# sch_ma_NCS2.net
KiCad netlist of a schematic drawn in Altium Designer
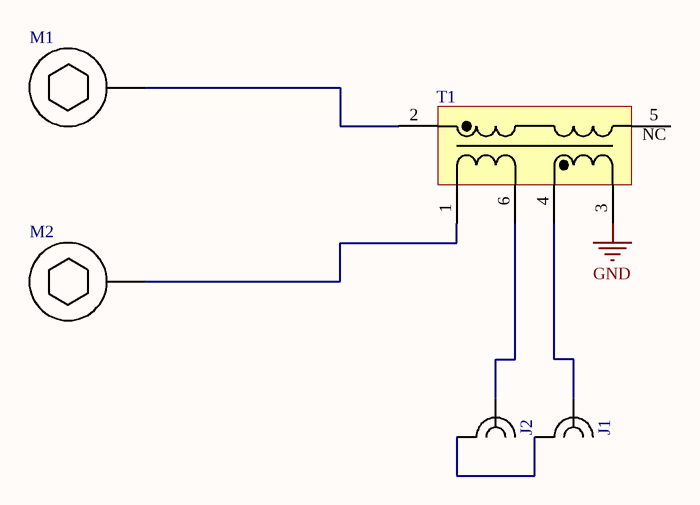
[diagram p0: schéma_NCS2.SchDoc]

(export (version "E")
  (design (tool "Eeschema 10.0.6"))
  (components
    (comp (ref "J1")
      (value "CONSMA001-G")
      (footprint "SMA TH Vertical Linx CONSMA001-G")
      (description "SMA TH VERTICAL LINX CONSMA001-G")
      (libsource (lib "Connector") (part "SMA TH VERTICAL LINX CONSMA001-G"))
    )
    (comp (ref "J2")
      (value "CONSMA001-G")
      (footprint "SMA TH Vertical Linx CONSMA001-G")
      (description "SMA TH VERTICAL LINX CONSMA001-G")
      (libsource (lib "Connector") (part "SMA TH VERTICAL LINX CONSMA001-G"))
    )
    (comp (ref "M1")
      (value "~")
      (footprint "Screw Hex Socket M2.5X4 Connected")
      (description "Screw Hex Socket Connected BN610")
      (libsource (lib "Mechanic") (part "Screw Hex Socket Connected"))
    )
    (comp (ref "M2")
      (value "~")
      (footprint "Screw Hex Socket M2.5X4 Connected")
      (description "Screw Hex Socket Connected BN610")
      (libsource (lib "Mechanic") (part "Screw Hex Socket Connected"))
    )
    (comp (ref "T1")
      (value "{Value}")
      (footprint "NCS2-771-75+")
      (description "Mini-Circuits RF Transformer")
      (libsource (lib "Transformer") (part "NCS2-771-75+"))
    )
  )
  (nets
    (net (code "1") (name "GND") (class "Default")
      (node (ref "T1") (pin "3") (pinfunction "3_3") (pintype "passive"))
    )
    (net (code "2") (name "Net-(J1-Pad2)") (class "Default")
      (node (ref "J1") (pin "2") (pinfunction "2_2") (pintype "passive"))
      (node (ref "J2") (pin "2") (pinfunction "2_2") (pintype "passive"))
    )
    (net (code "3") (name "Net-(M1-Pad1)") (class "Default")
      (node (ref "M1") (pin "1") (pinfunction "1_1") (pintype "passive"))
      (node (ref "T1") (pin "2") (pinfunction "2_2") (pintype "passive"))
    )
    (net (code "4") (name "Net-(M2-Pad1)") (class "Default")
      (node (ref "M2") (pin "1") (pinfunction "1_1") (pintype "passive"))
      (node (ref "T1") (pin "1") (pinfunction "1_1") (pintype "passive"))
    )
    (net (code "5") (name "unconnected-(J1-Pad1)") (class "Default")
      (node (ref "J1") (pin "1") (pinfunction "1_1") (pintype "passive"))
    )
    (net (code "6") (name "unconnected-(J2-Pad1)") (class "Default")
      (node (ref "J2") (pin "1") (pinfunction "1_1") (pintype "passive"))
    )
    (net (code "7") (name "unconnected-(T1-Pad4)") (class "Default")
      (node (ref "T1") (pin "4") (pinfunction "4_4") (pintype "passive"))
    )
    (net (code "8") (name "unconnected-(T1-Pad5)") (class "Default")
      (node (ref "T1") (pin "5") (pinfunction "5_5") (pintype "passive"))
    )
    (net (code "9") (name "unconnected-(T1-Pad6)") (class "Default")
      (node (ref "T1") (pin "6") (pinfunction "6_6") (pintype "passive"))
    )
  )
)
